# CCR.net
KiCad netlist of a schematic drawn in EAGLE
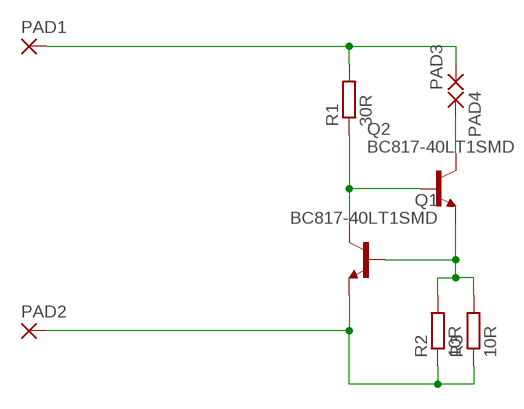
[diagram p0: schematic, sheet 1]

(export (version "E")
  (design (tool "Eeschema 10.0.6"))
  (components
    (comp (ref "PAD1")
      (value "2,15/1,0")
      (footprint "eagle-import:2,15_1,0")
      (libsource (lib "eagle-import") (part "2,15/1,0"))
    )
    (comp (ref "PAD2")
      (value "2,15/1,0")
      (footprint "eagle-import:2,15_1,0")
      (libsource (lib "eagle-import") (part "2,15/1,0"))
    )
    (comp (ref "PAD3")
      (value "2,15/1,0")
      (footprint "eagle-import:2,15_1,0")
      (libsource (lib "eagle-import") (part "2,15/1,0"))
    )
    (comp (ref "PAD4")
      (value "2,15/1,0")
      (footprint "eagle-import:2,15_1,0")
      (libsource (lib "eagle-import") (part "2,15/1,0"))
    )
    (comp (ref "Q1")
      (value "BC817-40LT1SMD")
      (footprint "eagle-import:SOT23-BEC")
      (libsource (lib "eagle-import") (part "BC817SMD-40LT1"))
    )
    (comp (ref "Q2")
      (value "BC817-40LT1SMD")
      (footprint "eagle-import:SOT23-BEC")
      (libsource (lib "eagle-import") (part "BC817SMD-40LT1"))
    )
    (comp (ref "R1")
      (value "30R")
      (footprint "eagle-import:R1206")
      (libsource (lib "eagle-import") (part "R_1206"))
    )
    (comp (ref "R2")
      (value "10R")
      (footprint "eagle-import:R1206")
      (libsource (lib "eagle-import") (part "R_1206"))
    )
    (comp (ref "R3")
      (value "10R")
      (footprint "eagle-import:R1206")
      (libsource (lib "eagle-import") (part "R_1206"))
    )
  )
  (nets
    (net (code "1") (name "Net-(PAD1-P)") (class "Default")
      (node (ref "PAD1") (pin "1") (pinfunction "P_1") (pintype "passive"))
      (node (ref "PAD3") (pin "1") (pinfunction "P_1") (pintype "passive"))
      (node (ref "R1") (pin "2") (pinfunction "2_2") (pintype "passive"))
    )
    (net (code "2") (name "Net-(PAD2-P)") (class "Default")
      (node (ref "PAD2") (pin "1") (pinfunction "P_1") (pintype "passive"))
      (node (ref "Q1") (pin "E") (pinfunction "E_E") (pintype "passive"))
      (node (ref "R2") (pin "1") (pinfunction "1_1") (pintype "passive"))
      (node (ref "R3") (pin "1") (pinfunction "1_1") (pintype "passive"))
    )
    (net (code "3") (name "Net-(PAD4-P)") (class "Default")
      (node (ref "PAD4") (pin "1") (pinfunction "P_1") (pintype "passive"))
      (node (ref "Q2") (pin "C") (pinfunction "C_C") (pintype "passive"))
    )
    (net (code "4") (name "Net-(Q1-PadB)") (class "Default")
      (node (ref "Q1") (pin "B") (pinfunction "B_B") (pintype "passive"))
      (node (ref "Q2") (pin "E") (pinfunction "E_E") (pintype "passive"))
      (node (ref "R2") (pin "2") (pinfunction "2_2") (pintype "passive"))
      (node (ref "R3") (pin "2") (pinfunction "2_2") (pintype "passive"))
    )
    (net (code "5") (name "Net-(Q1-PadC)") (class "Default")
      (node (ref "Q1") (pin "C") (pinfunction "C_C") (pintype "passive"))
      (node (ref "Q2") (pin "B") (pinfunction "B_B") (pintype "passive"))
      (node (ref "R1") (pin "1") (pinfunction "1_1") (pintype "passive"))
    )
  )
)
